# BSR049A.net
KiCad netlist of a schematic drawn in Altium Designer
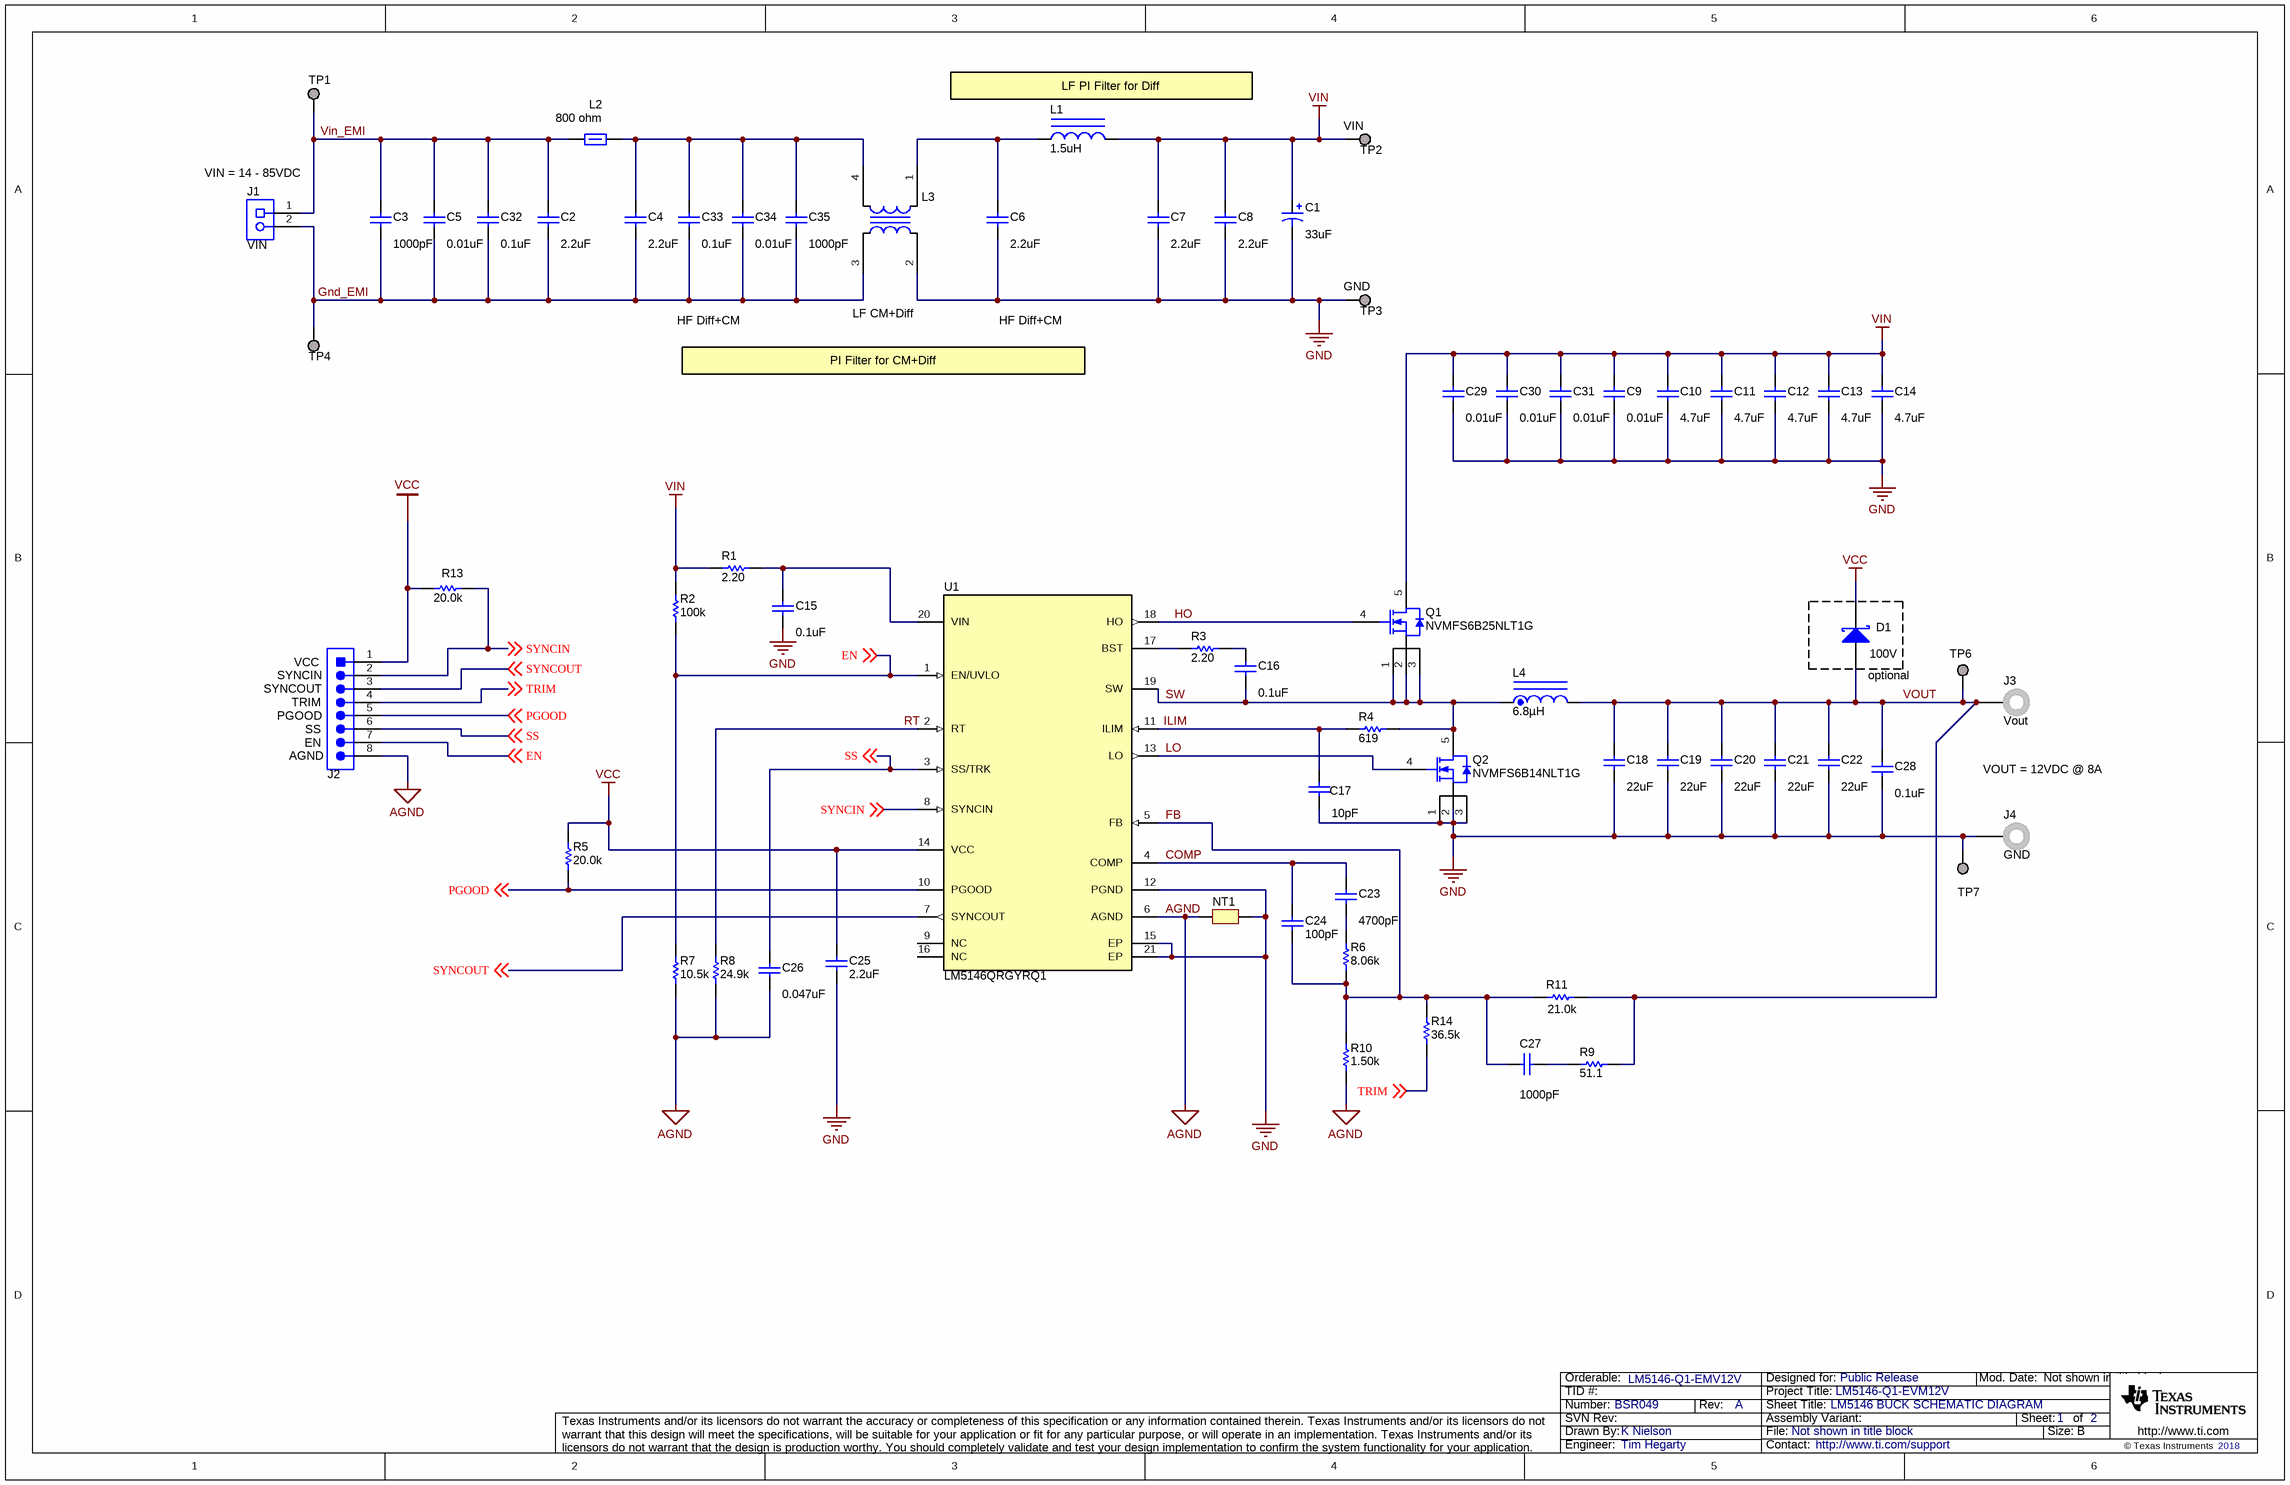
[diagram p0: BSR049A.SchDoc]

(export (version "E")
  (design (tool "Eeschema 10.0.6"))
  (components
    (comp (ref "C1")
      (value "EEE-FK2A330P")
      (footprint "SM_RADIAL_G")
      (description "CAP, AL, 33 uF, 100 V, +/- 20%, 0.7 ohm, AEC-Q200 Grade 2, SMD")
      (fields
        (field (name "MANUFACTURER") "Panasonic")
        (field (name "VALUEDISPLAYED") "33uF")
        (field (name "PUBLISHER") "Texas Instruments")
      )
      (libsource (lib "Altium Vault - TI") (part "Cap_Polarized"))
    )
    (comp (ref "C2")
      (value "CGA6N3X7R2A225K230AB")
      (footprint "1210_250")
      (description "CAP, CERM, 2.2 uF, 100 V, +/- 10%, X7R, AEC-Q200 Grade 1,")
      (fields
        (field (name "MANUFACTURER") "TDK")
        (field (name "VALUEDISPLAYED") "2.2uF")
        (field (name "PUBLISHER") "Texas Instruments")
      )
      (libsource (lib "Altium Vault - TI") (part "CMP-0009152-2"))
    )
    (comp (ref "C3")
      (value "CGA3E2X7R2A102K080AA")
      (footprint "0603L")
      (description "CAP, CERM, 1000 pF, 100 V, +/- 10%, X7R, AEC-Q200 Grade 1, 0603")
      (fields
        (field (name "MANUFACTURER") "TDK")
        (field (name "VALUEDISPLAYED") "1000pF")
        (field (name "PUBLISHER") "Texas Instruments")
      )
      (libsource (lib "Altium Vault - TI") (part "CMP-0007081-4"))
    )
    (comp (ref "C4")
      (value "CGA6N3X7R2A225K230AB")
      (footprint "1210_250")
      (description "CAP, CERM, 2.2 uF, 100 V, +/- 10%, X7R, AEC-Q200 Grade 1,")
      (fields
        (field (name "MANUFACTURER") "TDK")
        (field (name "VALUEDISPLAYED") "2.2uF")
        (field (name "PUBLISHER") "Texas Instruments")
      )
      (libsource (lib "Altium Vault - TI") (part "CMP-0009152-2"))
    )
    (comp (ref "C5")
      (value "GRM188R72A103KA01D")
      (footprint "0603L")
      (description "CAP, CERM, 0.01 uF, 100 V, +/- 10%, X7R, 0603")
      (fields
        (field (name "MANUFACTURER") "MuRata")
        (field (name "VALUEDISPLAYED") "0.01uF")
        (field (name "PUBLISHER") "Texas Instruments")
      )
      (libsource (lib "Altium Vault - TI") (part "CMP-0007468-5"))
    )
    (comp (ref "C6")
      (value "CGA6N3X7R2A225K230AB")
      (footprint "1210_250")
      (description "CAP, CERM, 2.2 uF, 100 V, +/- 10%, X7R, AEC-Q200 Grade 1,")
      (fields
        (field (name "MANUFACTURER") "TDK")
        (field (name "VALUEDISPLAYED") "2.2uF")
        (field (name "PUBLISHER") "Texas Instruments")
      )
      (libsource (lib "Altium Vault - TI") (part "Capacitor"))
    )
    (comp (ref "C7")
      (value "CGA6N3X7R2A225K230AB")
      (footprint "1210_250")
      (description "CAP, CERM, 2.2 uF, 100 V, +/- 10%, X7R, AEC-Q200 Grade 1,")
      (fields
        (field (name "MANUFACTURER") "TDK")
        (field (name "VALUEDISPLAYED") "2.2uF")
        (field (name "PUBLISHER") "Texas Instruments")
      )
      (libsource (lib "Altium Vault - TI") (part "Capacitor"))
    )
    (comp (ref "C8")
      (value "CGA6N3X7R2A225K230AB")
      (footprint "1210_250")
      (description "CAP, CERM, 2.2 uF, 100 V, +/- 10%, X7R, AEC-Q200 Grade 1,")
      (fields
        (field (name "MANUFACTURER") "TDK")
        (field (name "VALUEDISPLAYED") "2.2uF")
        (field (name "PUBLISHER") "Texas Instruments")
      )
      (libsource (lib "Altium Vault - TI") (part "Capacitor"))
    )
    (comp (ref "C9")
      (value "GRM188R72A103KA01D")
      (footprint "0603L")
      (description "CAP, CERM, 0.01 uF, 100 V, +/- 10%, X7R, 0603")
      (fields
        (field (name "MANUFACTURER") "MuRata")
        (field (name "VALUEDISPLAYED") "0.01uF")
        (field (name "PUBLISHER") "Texas Instruments")
      )
      (libsource (lib "Altium Vault - TI") (part "Capacitor"))
    )
    (comp (ref "C10")
      (value "C3225X7S2A475K200AE")
      (footprint "1210")
      (description "CAP, CERM, 4.7 uF, 100 V, +/- 10%, X7S, 1210")
      (fields
        (field (name "MANUFACTURER") "TDK")
        (field (name "VALUEDISPLAYED") "4.7uF")
        (field (name "PUBLISHER") "Texas Instruments")
      )
      (libsource (lib "Altium Vault - TI") (part "CMP-0009135-2"))
    )
    (comp (ref "C11")
      (value "C3225X7S2A475K200AE")
      (footprint "1210")
      (description "CAP, CERM, 4.7 uF, 100 V, +/- 10%, X7S, 1210")
      (fields
        (field (name "MANUFACTURER") "TDK")
        (field (name "VALUEDISPLAYED") "4.7uF")
        (field (name "PUBLISHER") "Texas Instruments")
      )
      (libsource (lib "Altium Vault - TI") (part "Capacitor"))
    )
    (comp (ref "C12")
      (value "C3225X7S2A475K200AE")
      (footprint "1210")
      (description "CAP, CERM, 4.7 uF, 100 V, +/- 10%, X7S, 1210")
      (fields
        (field (name "MANUFACTURER") "TDK")
        (field (name "VALUEDISPLAYED") "4.7uF")
        (field (name "PUBLISHER") "Texas Instruments")
      )
      (libsource (lib "Altium Vault - TI") (part "CMP-0009135-2"))
    )
    (comp (ref "C13")
      (value "C3225X7S2A475K200AE")
      (footprint "1210")
      (description "CAP, CERM, 4.7 uF, 100 V, +/- 10%, X7S, 1210")
      (fields
        (field (name "MANUFACTURER") "TDK")
        (field (name "VALUEDISPLAYED") "4.7uF")
        (field (name "PUBLISHER") "Texas Instruments")
      )
      (libsource (lib "Altium Vault - TI") (part "CMP-0009135-2"))
    )
    (comp (ref "C14")
      (value "C3225X7S2A475K200AE")
      (footprint "1210")
      (description "CAP, CERM, 4.7 uF, 100 V, +/- 10%, X7S, 1210")
      (fields
        (field (name "MANUFACTURER") "TDK")
        (field (name "VALUEDISPLAYED") "4.7uF")
        (field (name "PUBLISHER") "Texas Instruments")
      )
      (libsource (lib "Altium Vault - TI") (part "CMP-0009135-2"))
    )
    (comp (ref "C15")
      (value "CGA3E3X7S2A104K080AB")
      (footprint "0603L")
      (description "CAP, CERM, 0.1 uF, 100 V, +/- 10%, X7S, AEC-Q200 Grade 1, 0603")
      (fields
        (field (name "MANUFACTURER") "TDK")
        (field (name "VALUEDISPLAYED") "0.1uF")
        (field (name "PUBLISHER") "Texas Instruments")
      )
      (libsource (lib "Altium Vault - TI") (part "CMP-0007099-4"))
    )
    (comp (ref "C16")
      (value "CGA3E3X7S2A104K080AB")
      (footprint "0603L")
      (description "CAP, CERM, 0.1 uF, 100 V, +/- 10%, X7S, AEC-Q200 Grade 1, 0603")
      (fields
        (field (name "MANUFACTURER") "TDK")
        (field (name "VALUEDISPLAYED") "0.1uF")
        (field (name "PUBLISHER") "Texas Instruments")
      )
      (libsource (lib "Altium Vault - TI") (part "CMP-0007099-4"))
    )
    (comp (ref "C17")
      (value "885012006073")
      (footprint "0603L")
      (description "CAP, CERM, 10 pF, 100 V,+/- 5%, C0G/NP0, 0603")
      (fields
        (field (name "MANUFACTURER") "Wurth Elektronik")
        (field (name "VALUEDISPLAYED") "10pF")
        (field (name "PUBLISHER") "Texas Instruments")
      )
      (libsource (lib "Altium Vault - TI") (part "CMP-0078152-1"))
    )
    (comp (ref "C18")
      (value "TMK325B7226KMHT")
      (footprint "1210_270")
      (description "CAP, CERM, 22 uF, 25 V, +/- 10%, X7R, AEC-Q200 Grade 1, 1210")
      (fields
        (field (name "MANUFACTURER") "Taiyo Yuden")
        (field (name "VALUEDISPLAYED") "22uF")
        (field (name "PUBLISHER") "Texas Instruments")
      )
      (libsource (lib "Altium Vault - TI") (part "CMP-0009255-2"))
    )
    (comp (ref "C19")
      (value "TMK325B7226KMHT")
      (footprint "1210_270")
      (description "CAP, CERM, 22 uF, 25 V, +/- 10%, X7R, AEC-Q200 Grade 1, 1210")
      (fields
        (field (name "MANUFACTURER") "Taiyo Yuden")
        (field (name "VALUEDISPLAYED") "22uF")
        (field (name "PUBLISHER") "Texas Instruments")
      )
      (libsource (lib "Altium Vault - TI") (part "Capacitor"))
    )
    (comp (ref "C20")
      (value "TMK325B7226KMHT")
      (footprint "1210_270")
      (description "CAP, CERM, 22 uF, 25 V, +/- 10%, X7R, AEC-Q200 Grade 1, 1210")
      (fields
        (field (name "MANUFACTURER") "Taiyo Yuden")
        (field (name "VALUEDISPLAYED") "22uF")
        (field (name "PUBLISHER") "Texas Instruments")
      )
      (libsource (lib "Altium Vault - TI") (part "Capacitor"))
    )
    (comp (ref "C21")
      (value "TMK325B7226KMHT")
      (footprint "1210_270")
      (description "CAP, CERM, 22 uF, 25 V, +/- 10%, X7R, AEC-Q200 Grade 1, 1210")
      (fields
        (field (name "MANUFACTURER") "Taiyo Yuden")
        (field (name "VALUEDISPLAYED") "22uF")
        (field (name "PUBLISHER") "Texas Instruments")
      )
      (libsource (lib "Altium Vault - TI") (part "Capacitor"))
    )
    (comp (ref "C22")
      (value "TMK325B7226KMHT")
      (footprint "1210_270")
      (description "CAP, CERM, 22 uF, 25 V, +/- 10%, X7R, AEC-Q200 Grade 1, 1210")
      (fields
        (field (name "MANUFACTURER") "Taiyo Yuden")
        (field (name "VALUEDISPLAYED") "22uF")
        (field (name "PUBLISHER") "Texas Instruments")
      )
      (libsource (lib "Altium Vault - TI") (part "Capacitor"))
    )
    (comp (ref "C23")
      (value "GRM155R71C472KA01D")
      (footprint "0402")
      (description "CAP, CERM, 4700 pF, 16 V, +/- 10%, X7R, 0402")
      (fields
        (field (name "MANUFACTURER") "MuRata")
        (field (name "VALUEDISPLAYED") "4700pF")
        (field (name "PUBLISHER") "Texas Instruments")
      )
      (libsource (lib "Altium Vault - TI") (part "Capacitor"))
    )
    (comp (ref "C24")
      (value "CGA2B2C0G1H101J050BA")
      (footprint "0402")
      (description "CAP, CERM, 100 pF, 50 V, +/- 5%, C0G/NP0, AEC-Q200 Grade 1, 0402")
      (fields
        (field (name "VALUEDISPLAYED") "100pF")
        (field (name "MANUFACTURER") "TDK")
        (field (name "PUBLISHER") "Texas Instruments")
      )
      (libsource (lib "Altium Vault - TI") (part "Capacitor"))
    )
    (comp (ref "C25")
      (value "GRM21BR71E225KA73L")
      (footprint "0805_HV")
      (description "CAP, CERM, 2.2 uF, 25 V, +/- 10%, X7R, 0805")
      (fields
        (field (name "VALUEDISPLAYED") "2.2uF")
        (field (name "MANUFACTURER") "MuRata")
        (field (name "PUBLISHER") "Texas Instruments")
      )
      (libsource (lib "Altium Vault - TI") (part "CMP-0008342-2"))
    )
    (comp (ref "C26")
      (value "C1005X7R1C473K050BC")
      (footprint "0402")
      (description "CAP, CERM, 0.047 uF, 16 V, +/- 10%, X7R, 0402")
      (fields
        (field (name "MANUFACTURER") "TDK")
        (field (name "VALUEDISPLAYED") "0.047uF")
        (field (name "PUBLISHER") "Texas Instruments")
      )
      (libsource (lib "Altium Vault - TI") (part "Capacitor"))
    )
    (comp (ref "C27")
      (value "CGA2B2X7R1H102K050BA")
      (footprint "0402")
      (description "CAP, CERM, 1000 pF, 50 V, +/- 10%, X7R, AEC-Q200 Grade 1, 0402")
      (fields
        (field (name "MANUFACTURER") "TDK")
        (field (name "VALUEDISPLAYED") "1000pF")
        (field (name "PUBLISHER") "Texas Instruments")
      )
      (libsource (lib "Altium Vault - TI") (part "Capacitor"))
    )
    (comp (ref "C28")
      (value "CGA3E3X7S2A104K080AB")
      (footprint "0603L")
      (description "CAP, CERM, 0.1 uF, 100 V, +/- 10%, X7S, AEC-Q200 Grade 1, 0603")
      (fields
        (field (name "MANUFACTURER") "TDK")
        (field (name "VALUEDISPLAYED") "0.1uF")
        (field (name "PUBLISHER") "Texas Instruments")
      )
      (libsource (lib "Altium Vault - TI") (part "CMP-0007099-4"))
    )
    (comp (ref "C29")
      (value "GRM188R72A103KA01D")
      (footprint "0603L")
      (description "CAP, CERM, 0.01 uF, 100 V, +/- 10%, X7R, 0603")
      (fields
        (field (name "MANUFACTURER") "MuRata")
        (field (name "VALUEDISPLAYED") "0.01uF")
        (field (name "PUBLISHER") "Texas Instruments")
      )
      (libsource (lib "Altium Vault - TI") (part "CMP-0007468-5"))
    )
    (comp (ref "C30")
      (value "GRM188R72A103KA01D")
      (footprint "0603L")
      (description "CAP, CERM, 0.01 uF, 100 V, +/- 10%, X7R, 0603")
      (fields
        (field (name "MANUFACTURER") "MuRata")
        (field (name "VALUEDISPLAYED") "0.01uF")
        (field (name "PUBLISHER") "Texas Instruments")
      )
      (libsource (lib "Altium Vault - TI") (part "CMP-0007468-5"))
    )
    (comp (ref "C31")
      (value "GRM188R72A103KA01D")
      (footprint "0603L")
      (description "CAP, CERM, 0.01 uF, 100 V, +/- 10%, X7R, 0603")
      (fields
        (field (name "MANUFACTURER") "MuRata")
        (field (name "VALUEDISPLAYED") "0.01uF")
        (field (name "PUBLISHER") "Texas Instruments")
      )
      (libsource (lib "Altium Vault - TI") (part "CMP-0007468-5"))
    )
    (comp (ref "C32")
      (value "CGA3E3X7S2A104K080AB")
      (footprint "0603L")
      (description "CAP, CERM, 0.1 uF, 100 V, +/- 10%, X7S, AEC-Q200 Grade 1, 0603")
      (fields
        (field (name "MANUFACTURER") "TDK")
        (field (name "VALUEDISPLAYED") "0.1uF")
        (field (name "PUBLISHER") "Texas Instruments")
      )
      (libsource (lib "Altium Vault - TI") (part "CMP-0007099-4"))
    )
    (comp (ref "C33")
      (value "CGA3E3X7S2A104K080AB")
      (footprint "0603L")
      (description "CAP, CERM, 0.1 uF, 100 V, +/- 10%, X7S, AEC-Q200 Grade 1, 0603")
      (fields
        (field (name "MANUFACTURER") "TDK")
        (field (name "VALUEDISPLAYED") "0.1uF")
        (field (name "PUBLISHER") "Texas Instruments")
      )
      (libsource (lib "Altium Vault - TI") (part "CMP-0007099-4"))
    )
    (comp (ref "C34")
      (value "GRM188R72A103KA01D")
      (footprint "0603L")
      (description "CAP, CERM, 0.01 uF, 100 V, +/- 10%, X7R, 0603")
      (fields
        (field (name "MANUFACTURER") "MuRata")
        (field (name "VALUEDISPLAYED") "0.01uF")
        (field (name "PUBLISHER") "Texas Instruments")
      )
      (libsource (lib "Altium Vault - TI") (part "CMP-0007468-5"))
    )
    (comp (ref "C35")
      (value "CGA3E2X7R2A102K080AA")
      (footprint "0603L")
      (description "CAP, CERM, 1000 pF, 100 V, +/- 10%, X7R, AEC-Q200 Grade 1, 0603")
      (fields
        (field (name "MANUFACTURER") "TDK")
        (field (name "VALUEDISPLAYED") "1000pF")
        (field (name "PUBLISHER") "Texas Instruments")
      )
      (libsource (lib "Altium Vault - TI") (part "CMP-0007081-4"))
    )
    (comp (ref "D1")
      (value "100V")
      (footprint "SOD-523")
      (description "Diode, Schottky, 100 V, 0.2 A, SOD-523")
      (fields
        (field (name "MANUFACTURER") "STMicroelectronics")
        (field (name "PARTNUMBER") "BAT41KFILM")
        (field (name "PUBLISHER") "Texas Instruments")
      )
      (libsource (lib "Altium Vault - TI") (part "CMP-0028894-2"))
    )
    (comp (ref "J1")
      (value "VIN")
      (footprint "Phoenix_1984617")
      (description "Terminal Block, 3.5mm, 2x1, TH")
      (fields
        (field (name "MANUFACTURER") "Phoenix Contact")
        (field (name "PARTNUMBER") "1984617")
        (field (name "PUBLISHER") "Texas Instruments")
      )
      (libsource (lib "Altium Vault - TI") (part "CMP-0055519-1"))
    )
    (comp (ref "J2")
      (value "TSW-108-07-G-S")
      (footprint "TSW-108-07-G-S")
      (description "Header, 100mil, 8x1, Gold, TH")
      (fields (field (name "MANUFACTURER") "Samtec") (field (name "PUBLISHER") "Texas Instruments"))
      (libsource (lib "Altium Vault - TI") (part "CMP-0075419-1"))
    )
    (comp (ref "J3")
      (value "Vout")
      (footprint "Keystone575-8")
      (description "Standard Banana Jack, Uninsulated, 8.9mm")
      (fields
        (field (name "PARTNUMBER") "575-8")
        (field (name "MANUFACTURER") "Keystone")
        (field (name "PUBLISHER") "Texas Instruments")
      )
      (libsource (lib "Altium Vault - TI") (part "CMP-0055166-2"))
    )
    (comp (ref "J4")
      (value "GND")
      (footprint "Keystone575-8")
      (description "Standard Banana Jack, Uninsulated, 8.9mm")
      (fields
        (field (name "PARTNUMBER") "575-8")
        (field (name "MANUFACTURER") "Keystone")
        (field (name "PUBLISHER") "Texas Instruments")
      )
      (libsource (lib "Altium Vault - TI") (part "CMP-0055166-2"))
    )
    (comp (ref "L1")
      (value "VCMT063T-1R5MN5")
      (footprint "VCMT063T")
      (description "Inductor, Drum Core, Powdered Iron, 1.5 uH, 9 A, 0.0125 ohm, AEC-Q200 Grade 0, SMD")
      (fields
        (field (name "MANUFACTURER") "Cyntec")
        (field (name "VALUEDISPLAYED") "1.5uH")
        (field (name "PUBLISHER") "Texas Instruments")
      )
      (libsource (lib "Altium Vault - TI") (part "Inductor_Iron"))
    )
    (comp (ref "L2")
      (value "800 ohm")
      (footprint "2220_390")
      (description "Ferrite Bead, 800 ohm @ 100 MHz, 8 A, 2220")
      (fields
        (field (name "MANUFACTURER") "Laird-Signal Integrity Products")
        (field (name "PARTNUMBER") "HR2220V801R-10")
        (field (name "PUBLISHER") "Texas Instruments")
      )
      (libsource (lib "Altium Vault - TI") (part "CMP-0003396-1"))
    )
    (comp (ref "L3")
      (value "ACM12V-701-2PL-TL00")
      (footprint "TDK_ACM12V")
      (description "Coupled inductor,  ohm, AEC-Q200 Grade 1, SMD")
      (fields (field (name "MANUFACTURER") "TDK"))
      (libsource (lib "Altium Vault - TI") (part "INDUCTOR_COUPLED_14_23_NP"))
    )
    (comp (ref "L4")
      (value "VCHA105D-6R8MS6")
      (footprint "VCHA105D")
      (description "Inductor, Drum Core, Powdered Iron, 6.8 µH, 10.8 A, 0.014 ohm, AEC-Q200 Grade 0, SMD")
      (fields (field (name "MANUFACTURER") "Cyntec") (field (name "VALUEDISPLAYED") "6.8µH"))
      (libsource (lib "Altium Vault - TI") (part "Inductor_Iron_Polarity"))
    )
    (comp (ref "NT1")
      (value "net tie")
      (footprint "Net-Tie_10mil")
      (description "Single point connection between nets.")
      (libsource (lib "Altium Vault - TI") (part "CMP-0078142-2"))
    )
    (comp (ref "Q1")
      (value "NVMFS6B25NLT1G")
      (footprint "SO-8FL")
      (description "MOSFET, N-CH, 100 V, 8 A, AEC-Q101, SO-8FL")
      (fields (field (name "MANUFACTURER") "ON Semiconductor"))
      (libsource (lib "Altium Vault - TI") (part "MOSFET_N_D5G4S123"))
    )
    (comp (ref "Q2")
      (value "NVMFS6B14NLT1G")
      (footprint "SO-8FL")
      (description "MOSFET, N-CH, 100 V, 11 A, AEC-Q101, SO-8FL")
      (fields (field (name "MANUFACTURER") "ON Semiconductor"))
      (libsource (lib "Altium Vault - TI") (part "MOSFET_N_D5G4S123"))
    )
    (comp (ref "R1")
      (value "ERJ-3RQF2R2V")
      (footprint "0603L")
      (description "RES, 2.20, 1%, 0.1 W, 0603")
      (fields
        (field (name "MANUFACTURER") "Panasonic")
        (field (name "VALUEDISPLAYED") "2.20")
        (field (name "PUBLISHER") "Texas Instruments")
      )
      (libsource (lib "Altium Vault - TI") (part "CMP-0022711-2"))
    )
    (comp (ref "R2")
      (value "CRCW0603100KFKEA")
      (footprint "0603")
      (description "RES, 100 k, 1%, 0.1 W, AEC-Q200 Grade 0, 0603")
      (fields (field (name "MANUFACTURER") "Vishay-Dale") (field (name "VALUEDISPLAYED") "100k"))
      (libsource (lib "Altium Vault - TI") (part "Resistor"))
    )
    (comp (ref "R3")
      (value "ERJ-3RQF2R2V")
      (footprint "0603L")
      (description "RES, 2.20, 1%, 0.1 W, 0603")
      (fields
        (field (name "MANUFACTURER") "Panasonic")
        (field (name "VALUEDISPLAYED") "2.20")
        (field (name "PUBLISHER") "Texas Instruments")
      )
      (libsource (lib "Altium Vault - TI") (part "CMP-0022711-2"))
    )
    (comp (ref "R4")
      (value "CRCW0402619RFKED")
      (footprint "0402")
      (description "RES, 619, 1%, 0.063 W, AEC-Q200 Grade 0, 0402")
      (fields (field (name "MANUFACTURER") "Vishay-Dale") (field (name "VALUEDISPLAYED") "619"))
      (libsource (lib "Altium Vault - TI") (part "Resistor"))
    )
    (comp (ref "R5")
      (value "CRCW040220K0FKED")
      (footprint "0402")
      (description "RES, 20.0 k, 1%, 0.063 W, AEC-Q200 Grade 0, 0402")
      (fields (field (name "MANUFACTURER") "Vishay-Dale") (field (name "VALUEDISPLAYED") "20.0k"))
      (libsource (lib "Altium Vault - TI") (part "Resistor"))
    )
    (comp (ref "R6")
      (value "CRCW04028K06FKED")
      (footprint "0402")
      (description "RES, 8.06 k, 1%, 0.063 W, AEC-Q200 Grade 0, 0402")
      (fields (field (name "MANUFACTURER") "Vishay-Dale") (field (name "VALUEDISPLAYED") "8.06k"))
      (libsource (lib "Altium Vault - TI") (part "Resistor"))
    )
    (comp (ref "R7")
      (value "CRCW040210K5FKED")
      (footprint "0402")
      (description "RES, 10.5 k, 1%, 0.063 W, AEC-Q200 Grade 0, 0402")
      (fields (field (name "MANUFACTURER") "Vishay-Dale") (field (name "VALUEDISPLAYED") "10.5k"))
      (libsource (lib "Altium Vault - TI") (part "CMP-0025960-3"))
    )
    (comp (ref "R8")
      (value "CRCW040224K9FKED")
      (footprint "0402")
      (description "RES, 24.9 k, 1%, 0.063 W, AEC-Q200 Grade 0, 0402")
      (fields (field (name "MANUFACTURER") "Vishay-Dale") (field (name "VALUEDISPLAYED") "24.9k"))
      (libsource (lib "Altium Vault - TI") (part "Resistor"))
    )
    (comp (ref "R9")
      (value "CRCW040251R1FKED")
      (footprint "0402")
      (description "RES, 51.1, 1%, 0.063 W, AEC-Q200 Grade 0, 0402")
      (fields (field (name "MANUFACTURER") "Vishay-Dale") (field (name "VALUEDISPLAYED") "51.1"))
      (libsource (lib "Altium Vault - TI") (part "Resistor"))
    )
    (comp (ref "R10")
      (value "CRCW04021K50FKED")
      (footprint "0402")
      (description "RES, 1.50 k, 1%, 0.063 W, AEC-Q200 Grade 0, 0402")
      (fields (field (name "MANUFACTURER") "Vishay-Dale") (field (name "VALUEDISPLAYED") "1.50k"))
      (libsource (lib "Altium Vault - TI") (part "Resistor"))
    )
    (comp (ref "R11")
      (value "CRCW040221K0FKED")
      (footprint "0402")
      (description "RES, 21.0 k, 1%, 0.063 W, AEC-Q200 Grade 0, 0402")
      (fields (field (name "MANUFACTURER") "Vishay-Dale") (field (name "VALUEDISPLAYED") "21.0k"))
      (libsource (lib "Altium Vault - TI") (part "Resistor"))
    )
    (comp (ref "R13")
      (value "CRCW060320K0FKEA")
      (footprint "0603L")
      (description "RES, 20.0 k, 1%, 0.1 W, AEC-Q200 Grade 0, 0603")
      (fields (field (name "MANUFACTURER") "Vishay-Dale") (field (name "VALUEDISPLAYED") "20.0k"))
      (libsource (lib "Altium Vault - TI") (part "CMP-0022204-4"))
    )
    (comp (ref "R14")
      (value "CRCW040236K5FKED")
      (footprint "0402")
      (description "RES, 36.5 k, 1%, 0.063 W, AEC-Q200 Grade 0, 0402")
      (fields (field (name "MANUFACTURER") "Vishay-Dale") (field (name "VALUEDISPLAYED") "36.5k"))
      (libsource (lib "Altium Vault - TI") (part "Resistor"))
    )
    (comp (ref "TP1")
      (value "5017")
      (footprint "Keystone_5017")
      (description "PC Test Point, SMT")
      (fields (field (name "MANUFACTURER") "Keystone"))
      (libsource (lib "Altium Vault - TI") (part "CMP-0078225-1"))
    )
    (comp (ref "TP2")
      (value "VIN")
      (footprint "Keystone_5017")
      (description "PC Test Point, SMT")
      (fields (field (name "PARTNUMBER") "5017") (field (name "MANUFACTURER") "Keystone"))
      (libsource (lib "Altium Vault - TI") (part "CMP-0078225-1"))
    )
    (comp (ref "TP3")
      (value "GND")
      (footprint "Keystone_5017")
      (description "PC Test Point, SMT")
      (fields (field (name "PARTNUMBER") "5017") (field (name "MANUFACTURER") "Keystone"))
      (libsource (lib "Altium Vault - TI") (part "CMP-0078225-1"))
    )
    (comp (ref "TP4")
      (value "GND")
      (footprint "Keystone_5017")
      (description "PC Test Point, SMT")
      (fields (field (name "PARTNUMBER") "5017") (field (name "MANUFACTURER") "Keystone"))
      (libsource (lib "Altium Vault - TI") (part "CMP-0078225-1"))
    )
    (comp (ref "TP6")
      (value "GND")
      (footprint "Keystone_5017")
      (description "PC Test Point, SMT")
      (fields (field (name "PARTNUMBER") "5017") (field (name "MANUFACTURER") "Keystone"))
      (libsource (lib "Altium Vault - TI") (part "CMP-0078225-1"))
    )
    (comp (ref "TP7")
      (value "GND")
      (footprint "Keystone_5017")
      (description "PC Test Point, SMT")
      (fields (field (name "PARTNUMBER") "5017") (field (name "MANUFACTURER") "Keystone"))
      (libsource (lib "Altium Vault - TI") (part "CMP-0078225-1"))
    )
    (comp (ref "U1")
      (value "LM5146QRGYRQ1")
      (footprint "RGY0020B")
      (description "5.5-V to 100-V Synchronous Buck Controller With Wide Duty Cycle Range, RGY0020B (VQFN-20)")
      (fields
        (field (name "ALTERNATE PARTNUMBER") "LM5146QRGYTQ1")
        (field (name "MANUFACTURER") "Texas Instruments")
        (field (name "PARTNUMBER") "LM5146QRGYRQ1")
      )
      (libsource (lib "Altium Vault - TI") (part "CMP-0081848-1"))
    )
  )
  (nets
    (net (code "1") (name "/COMP") (class "Default")
      (node (ref "C23") (pin "1") (pinfunction "1_1") (pintype "passive"))
      (node (ref "C24") (pin "1") (pinfunction "1_1") (pintype "passive"))
      (node (ref "U1") (pin "4") (pinfunction "COMP_4") (pintype "passive"))
    )
    (net (code "2") (name "/FB") (class "Default")
      (node (ref "C24") (pin "2") (pinfunction "2_2") (pintype "passive"))
      (node (ref "C27") (pin "2") (pinfunction "2_2") (pintype "passive"))
      (node (ref "R10") (pin "2") (pinfunction "2_2") (pintype "passive"))
      (node (ref "R11") (pin "2") (pinfunction "2_2") (pintype "passive"))
      (node (ref "R14") (pin "2") (pinfunction "2_2") (pintype "passive"))
      (node (ref "R6") (pin "1") (pinfunction "1_1") (pintype "passive"))
      (node (ref "U1") (pin "5") (pinfunction "FB_5") (pintype "input"))
    )
    (net (code "3") (name "/Gnd_EMI") (class "Default")
      (node (ref "C2") (pin "2") (pinfunction "2_2") (pintype "passive"))
      (node (ref "C3") (pin "2") (pinfunction "2_2") (pintype "passive"))
      (node (ref "C32") (pin "2") (pinfunction "2_2") (pintype "passive"))
      (node (ref "C33") (pin "2") (pinfunction "2_2") (pintype "passive"))
      (node (ref "C34") (pin "2") (pinfunction "2_2") (pintype "passive"))
      (node (ref "C35") (pin "2") (pinfunction "2_2") (pintype "passive"))
      (node (ref "C4") (pin "2") (pinfunction "2_2") (pintype "passive"))
      (node (ref "C5") (pin "2") (pinfunction "2_2") (pintype "passive"))
      (node (ref "J1") (pin "2") (pinfunction "2_2") (pintype "passive"))
      (node (ref "L3") (pin "3") (pinfunction "3_3") (pintype "passive"))
      (node (ref "TP4") (pin "1") (pintype "passive"))
    )
    (net (code "4") (name "/HO") (class "Default")
      (node (ref "Q1") (pin "4") (pinfunction "G_4") (pintype "passive"))
      (node (ref "U1") (pin "18") (pinfunction "HO_18") (pintype "output"))
    )
    (net (code "5") (name "/ILIM") (class "Default")
      (node (ref "C17") (pin "1") (pinfunction "1_1") (pintype "passive"))
      (node (ref "R4") (pin "1") (pinfunction "1_1") (pintype "passive"))
      (node (ref "U1") (pin "11") (pinfunction "ILIM_11") (pintype "input"))
    )
    (net (code "6") (name "/LO") (class "Default")
      (node (ref "Q2") (pin "4") (pinfunction "G_4") (pintype "passive"))
      (node (ref "U1") (pin "13") (pinfunction "LO_13") (pintype "output"))
    )
    (net (code "7") (name "/RT") (class "Default")
      (node (ref "R8") (pin "1") (pinfunction "1_1") (pintype "passive"))
      (node (ref "U1") (pin "2") (pinfunction "RT_2") (pintype "input"))
    )
    (net (code "8") (name "/SW") (class "Default")
      (node (ref "C16") (pin "2") (pinfunction "2_2") (pintype "passive"))
      (node (ref "L4") (pin "1") (pinfunction "1_1") (pintype "passive"))
      (node (ref "Q1") (pin "1") (pinfunction "S_1") (pintype "passive"))
      (node (ref "Q1") (pin "2") (pinfunction "S_2") (pintype "passive"))
      (node (ref "Q1") (pin "3") (pinfunction "S_3") (pintype "passive"))
      (node (ref "Q2") (pin "5") (pinfunction "D_5") (pintype "passive"))
      (node (ref "R4") (pin "2") (pinfunction "2_2") (pintype "passive"))
      (node (ref "U1") (pin "19") (pinfunction "SW_19") (pintype "power_in"))
    )
    (net (code "9") (name "/VOUT") (class "Default")
      (node (ref "C18") (pin "1") (pinfunction "1_1") (pintype "passive"))
      (node (ref "C19") (pin "1") (pinfunction "1_1") (pintype "passive"))
      (node (ref "C20") (pin "1") (pinfunction "1_1") (pintype "passive"))
      (node (ref "C21") (pin "1") (pinfunction "1_1") (pintype "passive"))
      (node (ref "C22") (pin "1") (pinfunction "1_1") (pintype "passive"))
      (node (ref "C28") (pin "1") (pinfunction "1_1") (pintype "passive"))
      (node (ref "D1") (pin "2") (pinfunction "A_2") (pintype "passive"))
      (node (ref "J3") (pin "1") (pinfunction "1_1") (pintype "passive"))
      (node (ref "L4") (pin "2") (pinfunction "2_2") (pintype "passive"))
      (node (ref "R11") (pin "1") (pinfunction "1_1") (pintype "passive"))
      (node (ref "R9") (pin "1") (pinfunction "1_1") (pintype "passive"))
      (node (ref "TP6") (pin "1") (pintype "passive"))
    )
    (net (code "10") (name "/Vin_EMI") (class "Default")
      (node (ref "C2") (pin "1") (pinfunction "1_1") (pintype "passive"))
      (node (ref "C3") (pin "1") (pinfunction "1_1") (pintype "passive"))
      (node (ref "C32") (pin "1") (pinfunction "1_1") (pintype "passive"))
      (node (ref "C5") (pin "1") (pinfunction "1_1") (pintype "passive"))
      (node (ref "J1") (pin "1") (pinfunction "1_1") (pintype "passive"))
      (node (ref "L2") (pin "1") (pinfunction "1_1") (pintype "passive"))
      (node (ref "TP1") (pin "1") (pintype "passive"))
    )
    (net (code "11") (name "AGND") (class "Default")
      (node (ref "C26") (pin "1") (pinfunction "1_1") (pintype "passive"))
      (node (ref "J2") (pin "8") (pinfunction "8_8") (pintype "passive"))
      (node (ref "NT1") (pin "1") (pinfunction "1_1") (pintype "passive"))
      (node (ref "R10") (pin "1") (pinfunction "1_1") (pintype "passive"))
      (node (ref "R7") (pin "1") (pinfunction "1_1") (pintype "passive"))
      (node (ref "R8") (pin "2") (pinfunction "2_2") (pintype "passive"))
      (node (ref "U1") (pin "6") (pinfunction "AGND_6") (pintype "power_in"))
    )
    (net (code "12") (name "EN") (class "Default")
      (node (ref "J2") (pin "7") (pinfunction "7_7") (pintype "passive"))
      (node (ref "R2") (pin "2") (pinfunction "2_2") (pintype "passive"))
      (node (ref "R7") (pin "2") (pinfunction "2_2") (pintype "passive"))
      (node (ref "U1") (pin "1") (pinfunction "EN/UVLO_1") (pintype "input"))
    )
    (net (code "13") (name "GND") (class "Default")
      (node (ref "C1") (pin "2") (pinfunction "-_2") (pintype "passive"))
      (node (ref "C10") (pin "2") (pinfunction "2_2") (pintype "passive"))
      (node (ref "C11") (pin "2") (pinfunction "2_2") (pintype "passive"))
      (node (ref "C12") (pin "2") (pinfunction "2_2") (pintype "passive"))
      (node (ref "C13") (pin "2") (pinfunction "2_2") (pintype "passive"))
      (node (ref "C14") (pin "2") (pinfunction "2_2") (pintype "passive"))
      (node (ref "C15") (pin "2") (pinfunction "2_2") (pintype "passive"))
      (node (ref "C17") (pin "2") (pinfunction "2_2") (pintype "passive"))
      (node (ref "C18") (pin "2") (pinfunction "2_2") (pintype "passive"))
      (node (ref "C19") (pin "2") (pinfunction "2_2") (pintype "passive"))
      (node (ref "C20") (pin "2") (pinfunction "2_2") (pintype "passive"))
      (node (ref "C21") (pin "2") (pinfunction "2_2") (pintype "passive"))
      (node (ref "C22") (pin "2") (pinfunction "2_2") (pintype "passive"))
      (node (ref "C25") (pin "2") (pinfunction "2_2") (pintype "passive"))
      (node (ref "C28") (pin "2") (pinfunction "2_2") (pintype "passive"))
      (node (ref "C29") (pin "2") (pinfunction "2_2") (pintype "passive"))
      (node (ref "C30") (pin "2") (pinfunction "2_2") (pintype "passive"))
      (node (ref "C31") (pin "2") (pinfunction "2_2") (pintype "passive"))
      (node (ref "C6") (pin "2") (pinfunction "2_2") (pintype "passive"))
      (node (ref "C7") (pin "2") (pinfunction "2_2") (pintype "passive"))
      (node (ref "C8") (pin "2") (pinfunction "2_2") (pintype "passive"))
      (node (ref "C9") (pin "2") (pinfunction "2_2") (pintype "passive"))
      (node (ref "J4") (pin "1") (pinfunction "1_1") (pintype "passive"))
      (node (ref "L3") (pin "2") (pinfunction "2_2") (pintype "passive"))
      (node (ref "NT1") (pin "2") (pinfunction "2_2") (pintype "passive"))
      (node (ref "Q2") (pin "1") (pinfunction "S_1") (pintype "passive"))
      (node (ref "Q2") (pin "2") (pinfunction "S_2") (pintype "passive"))
      (node (ref "Q2") (pin "3") (pinfunction "S_3") (pintype "passive"))
      (node (ref "TP3") (pin "1") (pintype "passive"))
      (node (ref "TP7") (pin "1") (pintype "passive"))
      (node (ref "U1") (pin "12") (pinfunction "PGND_12") (pintype "power_in"))
      (node (ref "U1") (pin "15") (pinfunction "EP_15") (pintype "power_in"))
      (node (ref "U1") (pin "21") (pinfunction "EP_21") (pintype "power_in"))
    )
    (net (code "14") (name "Net-(C6-Pad1)") (class "Default")
      (node (ref "C6") (pin "1") (pinfunction "1_1") (pintype "passive"))
      (node (ref "L1") (pin "1") (pinfunction "1_1") (pintype "passive"))
      (node (ref "L3") (pin "1") (pinfunction "1_1") (pintype "passive"))
    )
    (net (code "15") (name "Net-(C16-Pad1)") (class "Default")
      (node (ref "C16") (pin "1") (pinfunction "1_1") (pintype "passive"))
      (node (ref "R3") (pin "2") (pinfunction "2_2") (pintype "passive"))
    )
    (net (code "16") (name "Net-(C23-Pad2)") (class "Default")
      (node (ref "C23") (pin "2") (pinfunction "2_2") (pintype "passive"))
      (node (ref "R6") (pin "2") (pinfunction "2_2") (pintype "passive"))
    )
    (net (code "17") (name "Net-(C27-Pad1)") (class "Default")
      (node (ref "C27") (pin "1") (pinfunction "1_1") (pintype "passive"))
      (node (ref "R9") (pin "2") (pinfunction "2_2") (pintype "passive"))
    )
    (net (code "18") (name "Net-(C33-Pad1)") (class "Default")
      (node (ref "C33") (pin "1") (pinfunction "1_1") (pintype "passive"))
      (node (ref "C34") (pin "1") (pinfunction "1_1") (pintype "passive"))
      (node (ref "C35") (pin "1") (pinfunction "1_1") (pintype "passive"))
      (node (ref "C4") (pin "1") (pinfunction "1_1") (pintype "passive"))
      (node (ref "L2") (pin "2") (pinfunction "2_2") (pintype "passive"))
      (node (ref "L3") (pin "4") (pinfunction "4_4") (pintype "passive"))
    )
    (net (code "19") (name "Net-(U1-BST)") (class "Default")
      (node (ref "R3") (pin "1") (pinfunction "1_1") (pintype "passive"))
      (node (ref "U1") (pin "17") (pinfunction "BST_17") (pintype "passive"))
    )
    (net (code "20") (name "Net-(U1-VIN)") (class "Default")
      (node (ref "C15") (pin "1") (pinfunction "1_1") (pintype "passive"))
      (node (ref "R1") (pin "2") (pinfunction "2_2") (pintype "passive"))
      (node (ref "U1") (pin "20") (pinfunction "VIN_20") (pintype "power_in"))
    )
    (net (code "21") (name "PGOOD") (class "Default")
      (node (ref "J2") (pin "5") (pinfunction "5_5") (pintype "passive"))
      (node (ref "R5") (pin "2") (pinfunction "2_2") (pintype "passive"))
      (node (ref "U1") (pin "10") (pinfunction "PGOOD_10") (pintype "open_collector"))
    )
    (net (code "22") (name "SS") (class "Default")
      (node (ref "C26") (pin "2") (pinfunction "2_2") (pintype "passive"))
      (node (ref "J2") (pin "6") (pinfunction "6_6") (pintype "passive"))
      (node (ref "U1") (pin "3") (pinfunction "SS/TRK_3") (pintype "input"))
    )
    (net (code "23") (name "SYNCIN") (class "Default")
      (node (ref "J2") (pin "2") (pinfunction "2_2") (pintype "passive"))
      (node (ref "R13") (pin "2") (pinfunction "2_2") (pintype "passive"))
      (node (ref "U1") (pin "8") (pinfunction "SYNCIN_8") (pintype "input"))
    )
    (net (code "24") (name "SYNCOUT") (class "Default")
      (node (ref "J2") (pin "3") (pinfunction "3_3") (pintype "passive"))
      (node (ref "U1") (pin "7") (pinfunction "SYNCOUT_7") (pintype "output"))
    )
    (net (code "25") (name "TRIM") (class "Default")
      (node (ref "J2") (pin "4") (pinfunction "4_4") (pintype "passive"))
      (node (ref "R14") (pin "1") (pinfunction "1_1") (pintype "passive"))
    )
    (net (code "26") (name "VCC") (class "Default")
      (node (ref "C25") (pin "1") (pinfunction "1_1") (pintype "passive"))
      (node (ref "D1") (pin "1") (pinfunction "K_1") (pintype "passive"))
      (node (ref "J2") (pin "1") (pinfunction "1_1") (pintype "passive"))
      (node (ref "R13") (pin "1") (pinfunction "1_1") (pintype "passive"))
      (node (ref "R5") (pin "1") (pinfunction "1_1") (pintype "passive"))
      (node (ref "U1") (pin "14") (pinfunction "VCC_14") (pintype "power_in"))
    )
    (net (code "27") (name "VIN") (class "Default")
      (node (ref "C1") (pin "1") (pinfunction "+_1") (pintype "passive"))
      (node (ref "C10") (pin "1") (pinfunction "1_1") (pintype "passive"))
      (node (ref "C11") (pin "1") (pinfunction "1_1") (pintype "passive"))
      (node (ref "C12") (pin "1") (pinfunction "1_1") (pintype "passive"))
      (node (ref "C13") (pin "1") (pinfunction "1_1") (pintype "passive"))
      (node (ref "C14") (pin "1") (pinfunction "1_1") (pintype "passive"))
      (node (ref "C29") (pin "1") (pinfunction "1_1") (pintype "passive"))
      (node (ref "C30") (pin "1") (pinfunction "1_1") (pintype "passive"))
      (node (ref "C31") (pin "1") (pinfunction "1_1") (pintype "passive"))
      (node (ref "C7") (pin "1") (pinfunction "1_1") (pintype "passive"))
      (node (ref "C8") (pin "1") (pinfunction "1_1") (pintype "passive"))
      (node (ref "C9") (pin "1") (pinfunction "1_1") (pintype "passive"))
      (node (ref "L1") (pin "2") (pinfunction "2_2") (pintype "passive"))
      (node (ref "Q1") (pin "5") (pinfunction "D_5") (pintype "passive"))
      (node (ref "R1") (pin "1") (pinfunction "1_1") (pintype "passive"))
      (node (ref "R2") (pin "1") (pinfunction "1_1") (pintype "passive"))
      (node (ref "TP2") (pin "1") (pintype "passive"))
    )
    (net (code "28") (name "unconnected-(U1-NC-Pad9)") (class "Default")
      (node (ref "U1") (pin "9") (pinfunction "NC_9") (pintype "passive"))
    )
    (net (code "29") (name "unconnected-(U1-NC-Pad16)") (class "Default")
      (node (ref "U1") (pin "16") (pinfunction "NC_16") (pintype "passive"))
    )
  )
)
